# SpectraPCB-V3.net
KiCad netlist of a schematic drawn in EAGLE
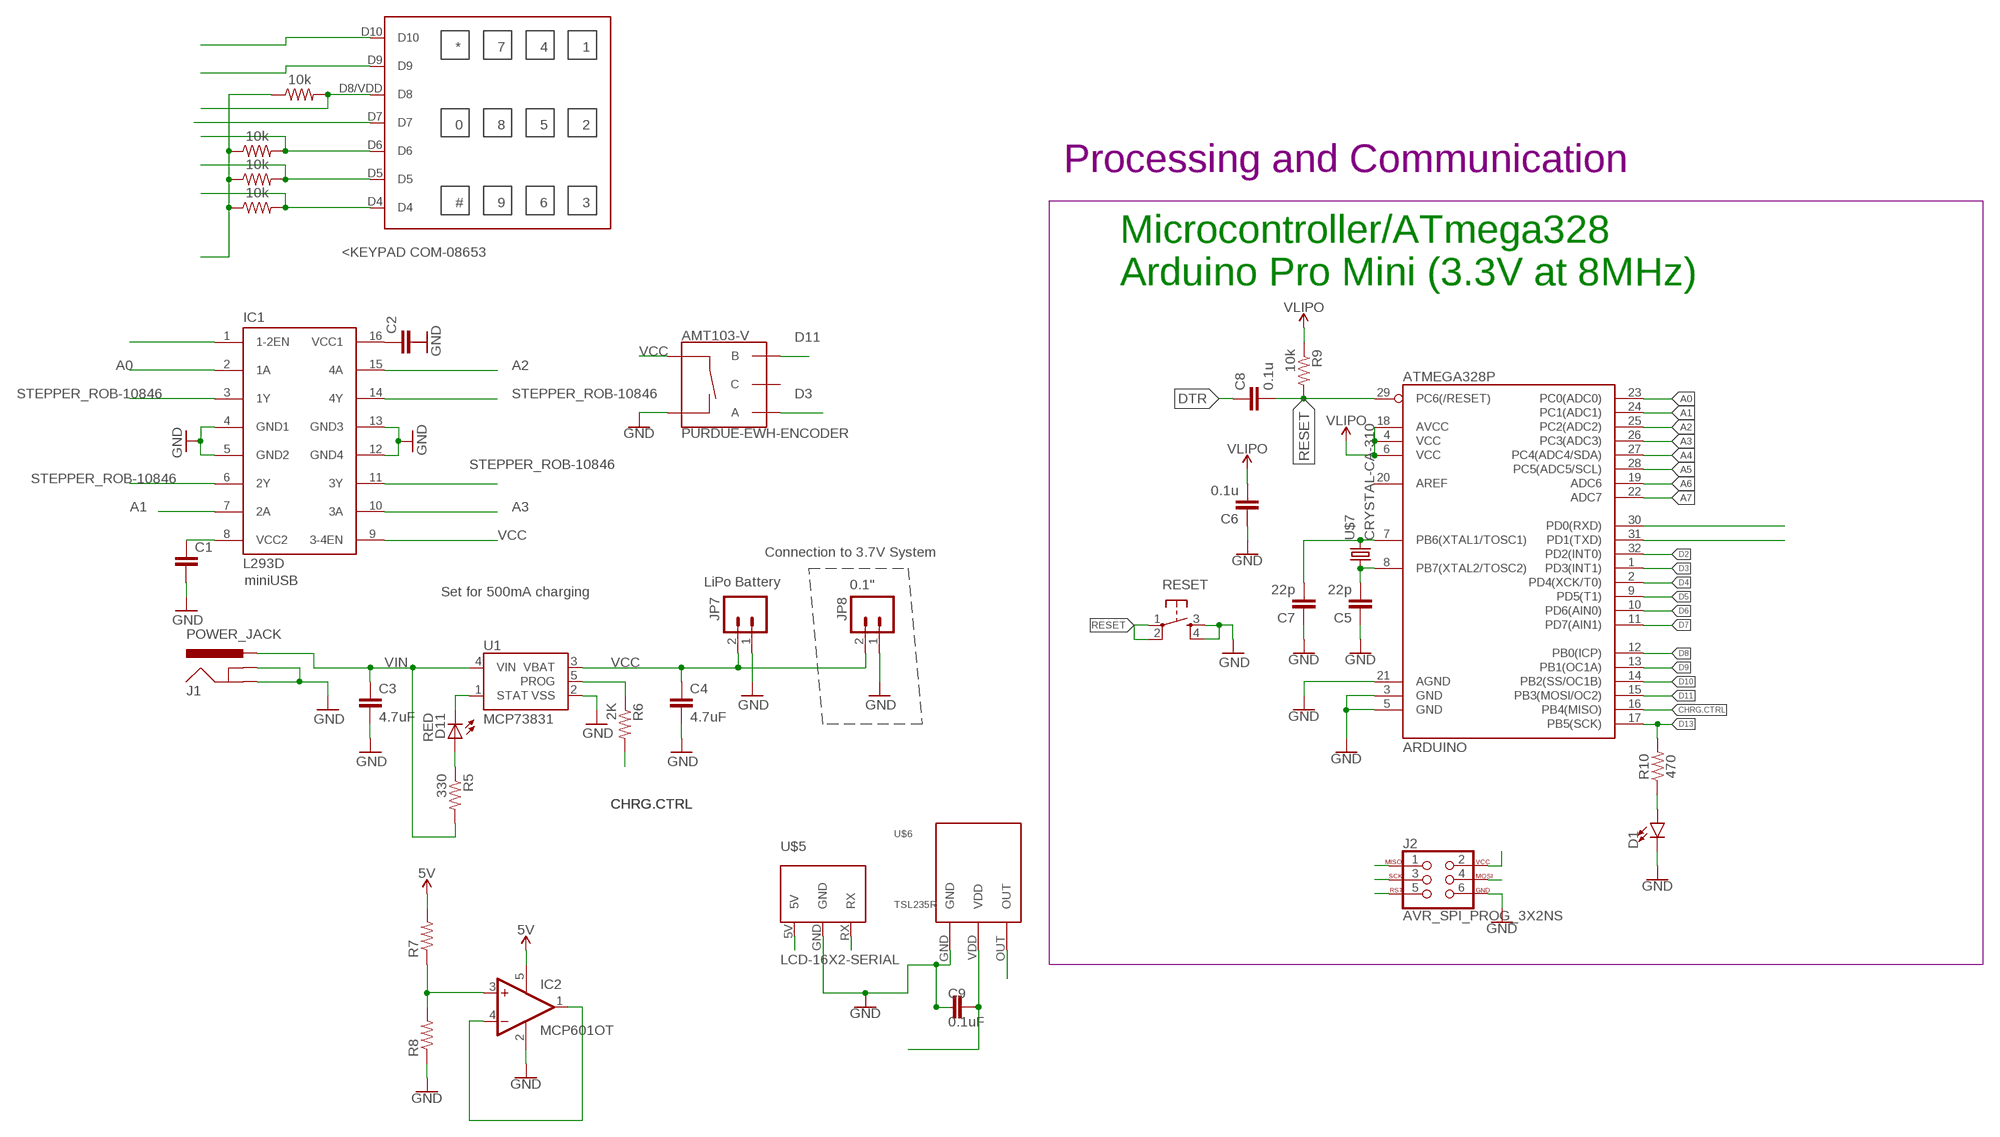
[diagram p0: schematic, sheet 1]

(export (version "E")
  (design (tool "Eeschema 10.0.6"))
  (components
    (comp (ref "AMT103-V")
      (value "PURDUE-EWH-ENCODER")
      (footprint "eagle-import:PURDUE-EWH-ENCODER")
      (libsource (lib "eagle-import") (part "PURDUE-EWH-ENCODER"))
    )
    (comp (ref "ARDUINO")
      (value "ATMEGA328P")
      (footprint "eagle-import:TQFP32-08")
      (libsource (lib "eagle-import") (part "ATMEGA328_SMT-OHMOD"))
    )
    (comp (ref "C1")
      (value "C-EUC0603")
      (footprint "eagle-import:C0603")
      (libsource (lib "eagle-import") (part "C-EUC0603"))
    )
    (comp (ref "C2")
      (value "C-EUC0402")
      (footprint "eagle-import:C0402")
      (libsource (lib "eagle-import") (part "C-EUC0402"))
    )
    (comp (ref "C3")
      (value "4.7uF")
      (footprint "eagle-import:0402-CAP")
      (libsource (lib "eagle-import") (part "CAP0402-CAP"))
    )
    (comp (ref "C4")
      (value "4.7uF")
      (footprint "eagle-import:0402-CAP")
      (libsource (lib "eagle-import") (part "CAP0402-CAP"))
    )
    (comp (ref "C5")
      (value "22p")
      (footprint "eagle-import:C0402")
      (libsource (lib "eagle-import") (part "CAPACITOR0402"))
    )
    (comp (ref "C6")
      (value "0.1u")
      (footprint "eagle-import:C0402")
      (libsource (lib "eagle-import") (part "CAPACITOR0402"))
    )
    (comp (ref "C7")
      (value "22p")
      (footprint "eagle-import:C0402")
      (libsource (lib "eagle-import") (part "CAPACITOR0402"))
    )
    (comp (ref "C8")
      (value "0.1u")
      (footprint "eagle-import:C0402")
      (libsource (lib "eagle-import") (part "C-EUC0402"))
    )
    (comp (ref "C9")
      (value "0.1uF")
      (footprint "eagle-import:0603")
      (libsource (lib "eagle-import") (part "0.1UF-0603-25V-(+80/-20%)"))
    )
    (comp (ref "D1")
      (value "LED5MM")
      (footprint "eagle-import:LED_5MM")
      (libsource (lib "eagle-import") (part "SparkFun-LED_LED5MM"))
    )
    (comp (ref "D11")
      (value "RED")
      (footprint "eagle-import:LED-0603")
      (libsource (lib "eagle-import") (part "LED0603"))
    )
    (comp (ref "IC1")
      (value "L293D")
      (footprint "eagle-import:DIL16")
      (libsource (lib "eagle-import") (part "L293D"))
    )
    (comp (ref "IC2")
      (value "MCP601OT")
      (footprint "eagle-import:SOT23-5")
      (libsource (lib "eagle-import") (part "MCP601OT"))
    )
    (comp (ref "J1")
      (value "POWER_JACK")
      (footprint "eagle-import:POWER_JACK_PTH")
      (libsource (lib "eagle-import") (part "POWER_JACK"))
    )
    (comp (ref "J2")
      (value "AVR_SPI_PROG_3X2NS")
      (footprint "eagle-import:2X3-NS")
      (libsource (lib "eagle-import") (part "AVR_SPI_PROG_3X2NS"))
    )
    (comp (ref "JP7")
      (value "LiPo Battery")
      (footprint "eagle-import:JST-2-SMD")
      (libsource (lib "eagle-import") (part "M02-JST-2MM-SMT"))
    )
    (comp (ref "JP8")
      (value "M02PTH")
      (footprint "eagle-import:1X02")
      (libsource (lib "eagle-import") (part "M02PTH"))
    )
    (comp (ref "R1")
      (value "10k")
      (footprint "eagle-import:0603")
      (libsource (lib "eagle-import") (part "10KOHM-0603-1/10W-1%"))
    )
    (comp (ref "R2")
      (value "10k")
      (footprint "eagle-import:0603")
      (libsource (lib "eagle-import") (part "10KOHM-0603-1/10W-1%"))
    )
    (comp (ref "R3")
      (value "10k")
      (footprint "eagle-import:0603")
      (libsource (lib "eagle-import") (part "10KOHM-0603-1/10W-1%"))
    )
    (comp (ref "R4")
      (value "10k")
      (footprint "eagle-import:0603")
      (libsource (lib "eagle-import") (part "10KOHM-0603-1/10W-1%"))
    )
    (comp (ref "R5")
      (value "330")
      (footprint "eagle-import:0402-RES")
      (libsource (lib "eagle-import") (part "RESISTOR0402-RES"))
    )
    (comp (ref "R6")
      (value "2K")
      (footprint "eagle-import:0402-RES")
      (libsource (lib "eagle-import") (part "RESISTOR0402-RES"))
    )
    (comp (ref "R7")
      (value "R-US_R0402")
      (footprint "eagle-import:R0402")
      (libsource (lib "eagle-import") (part "R-US_R0402"))
    )
    (comp (ref "R8")
      (value "R-US_R0402")
      (footprint "eagle-import:R0402")
      (libsource (lib "eagle-import") (part "R-US_R0402"))
    )
    (comp (ref "R9")
      (value "10k")
      (footprint "eagle-import:R0402")
      (libsource (lib "eagle-import") (part "RESISTOR0402"))
    )
    (comp (ref "R10")
      (value "470")
      (footprint "eagle-import:0603")
      (libsource (lib "eagle-import") (part "470OHM-0603-1/10W-1%"))
    )
    (comp (ref "RESET")
      (value "BUTTON-PTS830GG140")
      (footprint "eagle-import:BUTTON-GULLWING")
      (libsource (lib "eagle-import") (part "BUTTON-PTS830GG140"))
    )
    (comp (ref "U$1")
      (value "EWH_KEYPAD")
      (footprint "eagle-import:EWH_KEYPAD")
      (libsource (lib "eagle-import") (part "EWH_KEYPAD"))
    )
    (comp (ref "U$5")
      (value "LCD-16X2-SERIAL")
      (footprint "eagle-import:LCD-16X2-SERIAL")
      (libsource (lib "eagle-import") (part "LCD-16X2-SERIAL"))
    )
    (comp (ref "U$6")
      (value "TSL235R")
      (footprint "eagle-import:TSL235R")
      (libsource (lib "eagle-import") (part "TSL235R"))
    )
    (comp (ref "U$7")
      (value "CRYSTAL-CA-310")
      (footprint "eagle-import:CA-301")
      (libsource (lib "eagle-import") (part "CRYSTAL-CA-310"))
    )
    (comp (ref "U1")
      (value "MCP73831")
      (footprint "eagle-import:SOT23-5")
      (libsource (lib "eagle-import") (part "MCP73831"))
    )
  )
  (nets
    (net (code "1") (name "/D1") (class "Default")
      (node (ref "ARDUINO") (pin "31") (pinfunction "PD1(TXD)_31") (pintype "bidirectional"))
      (node (ref "U$5") (pin "RX") (pinfunction "RX_RX") (pintype "bidirectional"))
    )
    (net (code "2") (name "/STEPPER_ROB-10846") (class "Default")
      (node (ref "IC1") (pin "11") (pinfunction "3Y_11") (pintype "output"))
      (node (ref "IC1") (pin "14") (pinfunction "4Y_14") (pintype "output"))
      (node (ref "IC1") (pin "3") (pinfunction "1Y_3") (pintype "output"))
      (node (ref "IC1") (pin "6") (pinfunction "2Y_6") (pintype "output"))
    )
    (net (code "3") (name "/VCC") (class "Default")
      (node (ref "AMT103-V") (pin "SW+") (pinfunction "SW+_SW+") (pintype "bidirectional"))
      (node (ref "C4") (pin "1") (pinfunction "1_1") (pintype "passive"))
      (node (ref "C9") (pin "2") (pinfunction "2_2") (pintype "passive"))
      (node (ref "IC1") (pin "1") (pinfunction "1-2EN_1") (pintype "input"))
      (node (ref "IC1") (pin "9") (pinfunction "3-4EN_9") (pintype "input"))
      (node (ref "JP7") (pin "2") (pinfunction "2_2") (pintype "passive"))
      (node (ref "JP8") (pin "2") (pinfunction "2_2") (pintype "passive"))
      (node (ref "U$5") (pin "5V") (pinfunction "5V_5V") (pintype "bidirectional"))
      (node (ref "U$6") (pin "VDD") (pinfunction "VDD_VDD") (pintype "bidirectional"))
      (node (ref "U1") (pin "3") (pinfunction "VBAT_3") (pintype "power_in"))
    )
    (net (code "4") (name "/VIN") (class "Default")
      (node (ref "C3") (pin "1") (pinfunction "1_1") (pintype "passive"))
      (node (ref "J1") (pin "PWR") (pinfunction "PWR_PWR") (pintype "bidirectional"))
      (node (ref "R5") (pin "2") (pinfunction "2_2") (pintype "passive"))
      (node (ref "U1") (pin "4") (pinfunction "VIN_4") (pintype "power_in"))
    )
    (net (code "5") (name "5V") (class "Default")
      (node (ref "IC2") (pin "5") (pinfunction "V+_5") (pintype "power_in"))
      (node (ref "R7") (pin "2") (pinfunction "2_2") (pintype "passive"))
    )
    (net (code "6") (name "A0") (class "Default")
      (node (ref "ARDUINO") (pin "23") (pinfunction "PC0(ADC0)_23") (pintype "bidirectional"))
      (node (ref "IC1") (pin "2") (pinfunction "1A_2") (pintype "input"))
    )
    (net (code "7") (name "A1") (class "Default")
      (node (ref "ARDUINO") (pin "24") (pinfunction "PC1(ADC1)_24") (pintype "bidirectional"))
      (node (ref "IC1") (pin "7") (pinfunction "2A_7") (pintype "input"))
    )
    (net (code "8") (name "A2") (class "Default")
      (node (ref "ARDUINO") (pin "25") (pinfunction "PC2(ADC2)_25") (pintype "bidirectional"))
      (node (ref "IC1") (pin "15") (pinfunction "4A_15") (pintype "input"))
    )
    (net (code "9") (name "A3") (class "Default")
      (node (ref "ARDUINO") (pin "26") (pinfunction "PC3(ADC3)_26") (pintype "bidirectional"))
      (node (ref "IC1") (pin "10") (pinfunction "3A_10") (pintype "input"))
    )
    (net (code "10") (name "A4") (class "Default")
      (node (ref "ARDUINO") (pin "27") (pinfunction "PC4(ADC4/SDA)_27") (pintype "bidirectional"))
    )
    (net (code "11") (name "A5") (class "Default")
      (node (ref "ARDUINO") (pin "28") (pinfunction "PC5(ADC5/SCL)_28") (pintype "bidirectional"))
    )
    (net (code "12") (name "A6") (class "Default")
      (node (ref "ARDUINO") (pin "19") (pinfunction "ADC6_19") (pintype "bidirectional"))
    )
    (net (code "13") (name "A7") (class "Default")
      (node (ref "ARDUINO") (pin "22") (pinfunction "ADC7_22") (pintype "bidirectional"))
    )
    (net (code "14") (name "CHRG.CTRL") (class "Default")
      (node (ref "ARDUINO") (pin "16") (pinfunction "PB4(MISO)_16") (pintype "bidirectional"))
      (node (ref "R6") (pin "2") (pinfunction "2_2") (pintype "passive"))
    )
    (net (code "15") (name "D2") (class "Default")
      (node (ref "ARDUINO") (pin "32") (pinfunction "PD2(INT0)_32") (pintype "bidirectional"))
      (node (ref "U$6") (pin "OUT") (pinfunction "OUT_OUT") (pintype "bidirectional"))
    )
    (net (code "16") (name "D3") (class "Default")
      (node (ref "AMT103-V") (pin "A") (pinfunction "A_A") (pintype "bidirectional"))
      (node (ref "ARDUINO") (pin "1") (pinfunction "PD3(INT1)_1") (pintype "bidirectional"))
    )
    (net (code "17") (name "D4") (class "Default")
      (node (ref "ARDUINO") (pin "2") (pinfunction "PD4(XCK/T0)_2") (pintype "bidirectional"))
      (node (ref "R4") (pin "2") (pinfunction "2_2") (pintype "passive"))
      (node (ref "U$1") (pin "D4") (pinfunction "D4_D4") (pintype "bidirectional"))
    )
    (net (code "18") (name "D5") (class "Default")
      (node (ref "ARDUINO") (pin "9") (pinfunction "PD5(T1)_9") (pintype "bidirectional"))
      (node (ref "R3") (pin "2") (pinfunction "2_2") (pintype "passive"))
      (node (ref "U$1") (pin "D5") (pinfunction "D5_D5") (pintype "bidirectional"))
    )
    (net (code "19") (name "D6") (class "Default")
      (node (ref "ARDUINO") (pin "10") (pinfunction "PD6(AIN0)_10") (pintype "bidirectional"))
      (node (ref "R2") (pin "2") (pinfunction "2_2") (pintype "passive"))
      (node (ref "U$1") (pin "D6") (pinfunction "D6_D6") (pintype "bidirectional"))
    )
    (net (code "20") (name "D7") (class "Default")
      (node (ref "ARDUINO") (pin "11") (pinfunction "PD7(AIN1)_11") (pintype "bidirectional"))
      (node (ref "U$1") (pin "D7") (pinfunction "D7_D7") (pintype "bidirectional"))
    )
    (net (code "21") (name "D8") (class "Default")
      (node (ref "ARDUINO") (pin "12") (pinfunction "PB0(ICP)_12") (pintype "bidirectional"))
      (node (ref "R1") (pin "2") (pinfunction "2_2") (pintype "passive"))
      (node (ref "U$1") (pin "D8/VDD") (pinfunction "D8_D8/VDD") (pintype "bidirectional"))
    )
    (net (code "22") (name "D9") (class "Default")
      (node (ref "ARDUINO") (pin "13") (pinfunction "PB1(OC1A)_13") (pintype "bidirectional"))
      (node (ref "U$1") (pin "D9") (pinfunction "D9_D9") (pintype "bidirectional"))
    )
    (net (code "23") (name "D10") (class "Default")
      (node (ref "ARDUINO") (pin "14") (pinfunction "PB2(SS/OC1B)_14") (pintype "bidirectional"))
      (node (ref "U$1") (pin "D10") (pinfunction "D10_D10") (pintype "bidirectional"))
    )
    (net (code "24") (name "D11") (class "Default")
      (node (ref "AMT103-V") (pin "B") (pinfunction "B_B") (pintype "bidirectional"))
      (node (ref "ARDUINO") (pin "15") (pinfunction "PB3(MOSI/OC2)_15") (pintype "bidirectional"))
    )
    (net (code "25") (name "D13") (class "Default")
      (node (ref "ARDUINO") (pin "17") (pinfunction "PB5(SCK)_17") (pintype "bidirectional"))
      (node (ref "R10") (pin "2") (pinfunction "2_2") (pintype "passive"))
    )
    (net (code "26") (name "DTR") (class "Default")
      (node (ref "C8") (pin "1") (pinfunction "1_1") (pintype "passive"))
    )
    (net (code "27") (name "GND") (class "Default")
      (node (ref "AMT103-V") (pin "SW-") (pinfunction "SW-_SW-") (pintype "bidirectional"))
      (node (ref "ARDUINO") (pin "21") (pinfunction "AGND_21") (pintype "bidirectional"))
      (node (ref "ARDUINO") (pin "3") (pinfunction "GND_3") (pintype "bidirectional"))
      (node (ref "ARDUINO") (pin "5") (pinfunction "GND_5") (pintype "bidirectional"))
      (node (ref "C1") (pin "2") (pinfunction "2_2") (pintype "passive"))
      (node (ref "C3") (pin "2") (pinfunction "2_2") (pintype "passive"))
      (node (ref "C4") (pin "2") (pinfunction "2_2") (pintype "passive"))
      (node (ref "C5") (pin "1") (pinfunction "1_1") (pintype "passive"))
      (node (ref "C6") (pin "1") (pinfunction "1_1") (pintype "passive"))
      (node (ref "C7") (pin "1") (pinfunction "1_1") (pintype "passive"))
      (node (ref "C9") (pin "1") (pinfunction "1_1") (pintype "passive"))
      (node (ref "D1") (pin "K") (pinfunction "C_K") (pintype "passive"))
      (node (ref "IC1") (pin "12") (pinfunction "GND4_12") (pintype "power_in"))
      (node (ref "IC1") (pin "13") (pinfunction "GND3_13") (pintype "power_in"))
      (node (ref "IC1") (pin "4") (pinfunction "GND1_4") (pintype "power_in"))
      (node (ref "IC1") (pin "5") (pinfunction "GND2_5") (pintype "power_in"))
      (node (ref "IC2") (pin "2") (pinfunction "V-_2") (pintype "power_in"))
      (node (ref "J1") (pin "GND") (pinfunction "GND_GND") (pintype "bidirectional"))
      (node (ref "J1") (pin "GNDBREAK") (pinfunction "GNDBREAK_GNDBREAK") (pintype "bidirectional"))
      (node (ref "J2") (pin "6") (pinfunction "6_6") (pintype "passive"))
      (node (ref "JP7") (pin "1") (pinfunction "1_1") (pintype "passive"))
      (node (ref "JP8") (pin "1") (pinfunction "1_1") (pintype "passive"))
      (node (ref "R8") (pin "1") (pinfunction "1_1") (pintype "passive"))
      (node (ref "RESET") (pin "3") (pinfunction "3_3") (pintype "passive"))
      (node (ref "RESET") (pin "4") (pinfunction "4_4") (pintype "passive"))
      (node (ref "U$5") (pin "GND") (pinfunction "GND_GND") (pintype "bidirectional"))
      (node (ref "U$6") (pin "GND") (pinfunction "GND_GND") (pintype "bidirectional"))
      (node (ref "U1") (pin "2") (pinfunction "VSS_2") (pintype "power_in"))
    )
    (net (code "28") (name "Net-(ARDUINO-PB6(XTAL1{slash}TOSC1))") (class "Default")
      (node (ref "ARDUINO") (pin "7") (pinfunction "PB6(XTAL1/TOSC1)_7") (pintype "bidirectional"))
      (node (ref "C7") (pin "2") (pinfunction "2_2") (pintype "passive"))
      (node (ref "U$7") (pin "2") (pinfunction "2_2") (pintype "passive"))
    )
    (net (code "29") (name "Net-(ARDUINO-PB7(XTAL2{slash}TOSC2))") (class "Default")
      (node (ref "ARDUINO") (pin "8") (pinfunction "PB7(XTAL2/TOSC2)_8") (pintype "bidirectional"))
      (node (ref "C5") (pin "2") (pinfunction "2_2") (pintype "passive"))
      (node (ref "U$7") (pin "1") (pinfunction "1_1") (pintype "passive"))
    )
    (net (code "30") (name "Net-(D1-PadA)") (class "Default")
      (node (ref "D1") (pin "A") (pinfunction "A_A") (pintype "passive"))
      (node (ref "R10") (pin "1") (pinfunction "1_1") (pintype "passive"))
    )
    (net (code "31") (name "Net-(D11-PadA)") (class "Default")
      (node (ref "D11") (pin "A") (pinfunction "A_A") (pintype "passive"))
      (node (ref "R5") (pin "1") (pinfunction "1_1") (pintype "passive"))
    )
    (net (code "32") (name "Net-(IC1-VCC1)") (class "Default")
      (node (ref "C2") (pin "1") (pinfunction "1_1") (pintype "passive"))
      (node (ref "IC1") (pin "16") (pinfunction "VCC1_16") (pintype "power_in"))
    )
    (net (code "33") (name "Net-(IC1-VCC2)") (class "Default")
      (node (ref "C1") (pin "1") (pinfunction "1_1") (pintype "passive"))
      (node (ref "IC1") (pin "8") (pinfunction "VCC2_8") (pintype "power_in"))
    )
    (net (code "34") (name "Net-(IC2-+IN)") (class "Default")
      (node (ref "IC2") (pin "3") (pinfunction "+IN_3") (pintype "input"))
      (node (ref "R7") (pin "1") (pinfunction "1_1") (pintype "passive"))
      (node (ref "R8") (pin "2") (pinfunction "2_2") (pintype "passive"))
    )
    (net (code "35") (name "Net-(IC2--IN)") (class "Default")
      (node (ref "IC2") (pin "1") (pinfunction "OUT_1") (pintype "output"))
      (node (ref "IC2") (pin "4") (pinfunction "-IN_4") (pintype "input"))
    )
    (net (code "36") (name "Net-(R1-Pad1)") (class "Default")
      (node (ref "R1") (pin "1") (pinfunction "1_1") (pintype "passive"))
      (node (ref "R2") (pin "1") (pinfunction "1_1") (pintype "passive"))
      (node (ref "R3") (pin "1") (pinfunction "1_1") (pintype "passive"))
      (node (ref "R4") (pin "1") (pinfunction "1_1") (pintype "passive"))
    )
    (net (code "37") (name "Net-(U1-PROG)") (class "Default")
      (node (ref "R6") (pin "1") (pinfunction "1_1") (pintype "passive"))
      (node (ref "U1") (pin "5") (pinfunction "PROG_5") (pintype "input"))
    )
    (net (code "38") (name "Net-(U1-STAT)") (class "Default")
      (node (ref "D11") (pin "C") (pinfunction "C_C") (pintype "passive"))
      (node (ref "U1") (pin "1") (pinfunction "STAT_1") (pintype "output"))
    )
    (net (code "39") (name "RESET") (class "Default")
      (node (ref "ARDUINO") (pin "29") (pinfunction "PC6(/RESET)_29") (pintype "bidirectional"))
      (node (ref "C8") (pin "2") (pinfunction "2_2") (pintype "passive"))
      (node (ref "R9") (pin "2") (pinfunction "2_2") (pintype "passive"))
      (node (ref "RESET") (pin "1") (pinfunction "1_1") (pintype "passive"))
      (node (ref "RESET") (pin "2") (pinfunction "2_2") (pintype "passive"))
    )
    (net (code "40") (name "VLIPO") (class "Default")
      (node (ref "ARDUINO") (pin "18") (pinfunction "AVCC_18") (pintype "bidirectional"))
      (node (ref "ARDUINO") (pin "4") (pinfunction "VCC_4") (pintype "bidirectional"))
      (node (ref "ARDUINO") (pin "6") (pinfunction "VCC_6") (pintype "bidirectional"))
      (node (ref "C6") (pin "2") (pinfunction "2_2") (pintype "passive"))
      (node (ref "R9") (pin "1") (pinfunction "1_1") (pintype "passive"))
    )
    (net (code "41") (name "unconnected-(AMT103-V-PadC)") (class "Default")
      (node (ref "AMT103-V") (pin "C") (pinfunction "C_C") (pintype "bidirectional"))
    )
    (net (code "42") (name "unconnected-(ARDUINO-AREF-Pad20)") (class "Default")
      (node (ref "ARDUINO") (pin "20") (pinfunction "AREF_20") (pintype "bidirectional"))
    )
    (net (code "43") (name "unconnected-(ARDUINO-PD0(RXD)-Pad30)") (class "Default")
      (node (ref "ARDUINO") (pin "30") (pinfunction "PD0(RXD)_30") (pintype "bidirectional"))
    )
    (net (code "44") (name "unconnected-(C2-Pad2)") (class "Default")
      (node (ref "C2") (pin "2") (pinfunction "2_2") (pintype "passive"))
    )
    (net (code "45") (name "unconnected-(J2-Pad1)") (class "Default")
      (node (ref "J2") (pin "1") (pinfunction "1_1") (pintype "passive"))
    )
    (net (code "46") (name "unconnected-(J2-Pad2)") (class "Default")
      (node (ref "J2") (pin "2") (pinfunction "2_2") (pintype "passive"))
    )
    (net (code "47") (name "unconnected-(J2-Pad3)") (class "Default")
      (node (ref "J2") (pin "3") (pinfunction "3_3") (pintype "passive"))
    )
    (net (code "48") (name "unconnected-(J2-Pad4)") (class "Default")
      (node (ref "J2") (pin "4") (pinfunction "4_4") (pintype "passive"))
    )
    (net (code "49") (name "unconnected-(J2-Pad5)") (class "Default")
      (node (ref "J2") (pin "5") (pinfunction "5_5") (pintype "passive"))
    )
  )
)
